# Grace_sFirstMicrocontroller.net
KiCad netlist of a schematic drawn in EAGLE
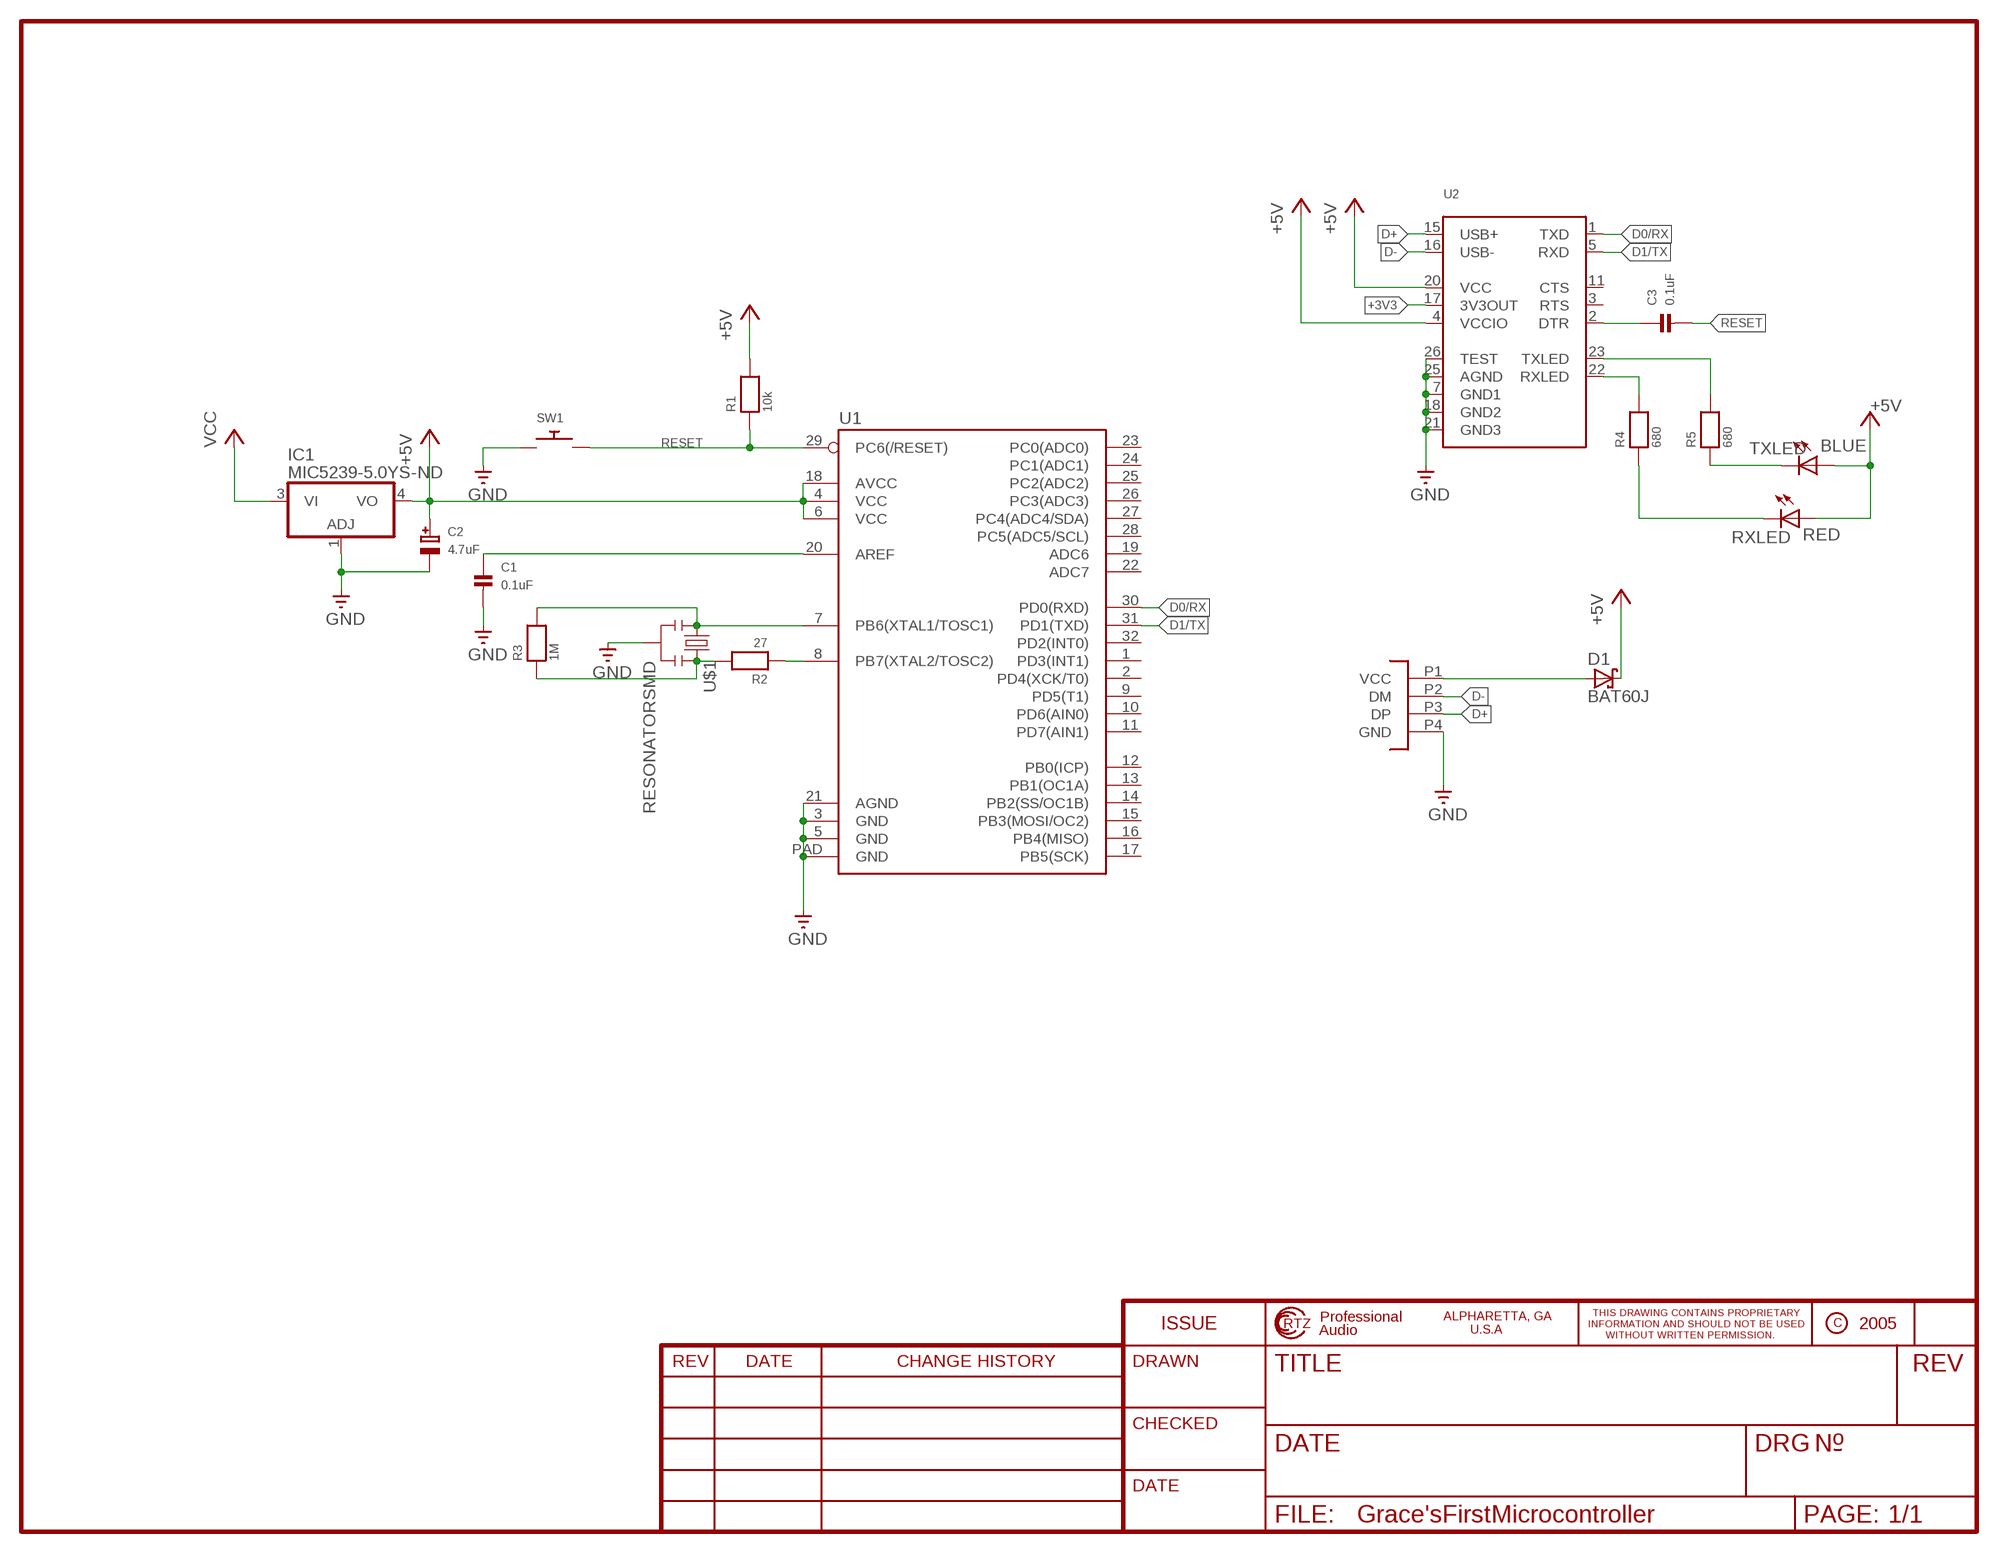
[diagram p0: schematic, sheet 1]

(export (version "E")
  (design (tool "Eeschema 10.0.6"))
  (components
    (comp (ref "C1")
      (value "0.1uF")
      (footprint "eagle-import:0603")
      (libsource (lib "eagle-import") (part "CAP_CERAMIC0603"))
    )
    (comp (ref "C2")
      (value "4.7uF")
      (footprint "eagle-import:EIA3216-18_A-R")
      (libsource (lib "eagle-import") (part "CAP_TANTALUMA/3216_REFLOW"))
    )
    (comp (ref "C3")
      (value "0.1uF")
      (footprint "eagle-import:0603")
      (libsource (lib "eagle-import") (part "CAP_CERAMIC0603"))
    )
    (comp (ref "D1")
      (value "BAT60J")
      (footprint "eagle-import:SOD323_ST")
      (libsource (lib "eagle-import") (part "BAT60J"))
    )
    (comp (ref "IC1")
      (value "MIC5239-5.0YS-ND")
      (footprint "eagle-import:SOT223")
      (libsource (lib "eagle-import") (part "317EMP"))
    )
    (comp (ref "J4A")
      (value "USB_TYPE_A_ONBOARD")
      (footprint "eagle-import:USB_TYPEA_ONBOARD")
      (libsource (lib "eagle-import") (part "USB_TYPE_A_ONBOARD"))
    )
    (comp (ref "R1")
      (value "10k")
      (footprint "eagle-import:0603")
      (libsource (lib "eagle-import") (part "RESISTOR0603"))
    )
    (comp (ref "R2")
      (value "27")
      (footprint "eagle-import:0603")
      (libsource (lib "eagle-import") (part "RESISTOR0603"))
    )
    (comp (ref "R3")
      (value "1M")
      (footprint "eagle-import:0603")
      (libsource (lib "eagle-import") (part "RESISTOR0603"))
    )
    (comp (ref "R4")
      (value "680")
      (footprint "eagle-import:0603")
      (libsource (lib "eagle-import") (part "RESISTOR0603"))
    )
    (comp (ref "R5")
      (value "680")
      (footprint "eagle-import:0603")
      (libsource (lib "eagle-import") (part "RESISTOR0603"))
    )
    (comp (ref "RXLED")
      (value "RED")
      (footprint "eagle-import:CHIPLED_0805")
      (libsource (lib "eagle-import") (part "LEDCHIPLED_0805"))
    )
    (comp (ref "SW1")
      (value "SWITCH_PUSHBUTTONEVQ-PE")
      (footprint "eagle-import:TACT_PANA-EVQ")
      (libsource (lib "eagle-import") (part "SWITCH_PUSHBUTTONEVQ-PE"))
    )
    (comp (ref "TXLED")
      (value "BLUE")
      (footprint "eagle-import:CHIPLED_0805")
      (libsource (lib "eagle-import") (part "LEDCHIPLED_0805"))
    )
    (comp (ref "U$1")
      (value "RESONATORSMD")
      (footprint "eagle-import:RESONATOR-SMD")
      (libsource (lib "eagle-import") (part "RESONATORSMD"))
    )
    (comp (ref "U1")
      (value "ATMEGA328P_MLFMLF32")
      (footprint "eagle-import:MLF32-PAD")
      (libsource (lib "eagle-import") (part "ATMEGA328P_MLFMLF32"))
    )
    (comp (ref "U2")
      (value "FT232RLSSOP28")
      (footprint "eagle-import:SSOP28DB")
      (libsource (lib "eagle-import") (part "FT232RLSSOP28"))
    )
  )
  (nets
    (net (code "1") (name "+3V3") (class "Default")
      (node (ref "U2") (pin "17") (pinfunction "3V3OUT_17") (pintype "power_in"))
    )
    (net (code "2") (name "+5V") (class "Default")
      (node (ref "C2") (pin "+") (pinfunction "+_+") (pintype "passive"))
      (node (ref "D1") (pin "C") (pinfunction "C_C") (pintype "passive"))
      (node (ref "IC1") (pin "4") (pinfunction "VO_4") (pintype "passive"))
      (node (ref "R1") (pin "2") (pinfunction "2_2") (pintype "passive"))
      (node (ref "RXLED") (pin "A") (pinfunction "A_A") (pintype "passive"))
      (node (ref "TXLED") (pin "A") (pinfunction "A_A") (pintype "passive"))
      (node (ref "U1") (pin "18") (pinfunction "AVCC_18") (pintype "bidirectional"))
      (node (ref "U1") (pin "4") (pinfunction "VCC_4") (pintype "bidirectional"))
      (node (ref "U1") (pin "6") (pinfunction "VCC_6") (pintype "bidirectional"))
      (node (ref "U2") (pin "20") (pinfunction "VCC_20") (pintype "power_in"))
      (node (ref "U2") (pin "4") (pinfunction "VCCIO_4") (pintype "power_in"))
    )
    (net (code "3") (name "D+") (class "Default")
      (node (ref "J4A") (pin "P3") (pinfunction "DP_P3") (pintype "bidirectional"))
      (node (ref "U2") (pin "15") (pinfunction "USB+_15") (pintype "bidirectional"))
    )
    (net (code "4") (name "D-") (class "Default")
      (node (ref "J4A") (pin "P2") (pinfunction "DM_P2") (pintype "bidirectional"))
      (node (ref "U2") (pin "16") (pinfunction "USB-_16") (pintype "bidirectional"))
    )
    (net (code "5") (name "D0{slash}RX") (class "Default")
      (node (ref "U1") (pin "30") (pinfunction "PD0(RXD)_30") (pintype "bidirectional"))
      (node (ref "U2") (pin "1") (pinfunction "TXD_1") (pintype "output"))
    )
    (net (code "6") (name "D1{slash}TX") (class "Default")
      (node (ref "U1") (pin "31") (pinfunction "PD1(TXD)_31") (pintype "bidirectional"))
      (node (ref "U2") (pin "5") (pinfunction "RXD_5") (pintype "input"))
    )
    (net (code "7") (name "GND") (class "Default")
      (node (ref "C1") (pin "2") (pinfunction "P$2_2") (pintype "passive"))
      (node (ref "C2") (pin "-") (pinfunction "-_-") (pintype "passive"))
      (node (ref "IC1") (pin "1") (pinfunction "ADJ_1") (pintype "input"))
      (node (ref "J4A") (pin "P4") (pinfunction "GND_P4") (pintype "bidirectional"))
      (node (ref "SW1") (pin "P$1") (pinfunction "P$1_P$1") (pintype "passive"))
      (node (ref "U$1") (pin "2") (pinfunction "2_2") (pintype "passive"))
      (node (ref "U1") (pin "21") (pinfunction "AGND_21") (pintype "bidirectional"))
      (node (ref "U1") (pin "3") (pinfunction "GND_3") (pintype "bidirectional"))
      (node (ref "U1") (pin "5") (pinfunction "GND_5") (pintype "bidirectional"))
      (node (ref "U1") (pin "PAD") (pinfunction "GND_PAD") (pintype "bidirectional"))
      (node (ref "U2") (pin "18") (pinfunction "GND2_18") (pintype "power_in"))
      (node (ref "U2") (pin "21") (pinfunction "GND3_21") (pintype "power_in"))
      (node (ref "U2") (pin "25") (pinfunction "AGND_25") (pintype "power_in"))
      (node (ref "U2") (pin "26") (pinfunction "TEST_26") (pintype "input"))
      (node (ref "U2") (pin "7") (pinfunction "GND1_7") (pintype "power_in"))
    )
    (net (code "8") (name "Net-(C1-P$1)") (class "Default")
      (node (ref "C1") (pin "1") (pinfunction "P$1_1") (pintype "passive"))
      (node (ref "U1") (pin "20") (pinfunction "AREF_20") (pintype "bidirectional"))
    )
    (net (code "9") (name "Net-(C3-P$1)") (class "Default")
      (node (ref "C3") (pin "1") (pinfunction "P$1_1") (pintype "passive"))
      (node (ref "U2") (pin "2") (pinfunction "DTR_2") (pintype "bidirectional"))
    )
    (net (code "10") (name "Net-(J4A-VCC)") (class "Default")
      (node (ref "D1") (pin "A") (pinfunction "A_A") (pintype "passive"))
      (node (ref "J4A") (pin "P1") (pinfunction "VCC_P1") (pintype "bidirectional"))
    )
    (net (code "11") (name "Net-(R2-Pad2)") (class "Default")
      (node (ref "R2") (pin "2") (pinfunction "2_2") (pintype "passive"))
      (node (ref "R3") (pin "1") (pinfunction "1_1") (pintype "passive"))
      (node (ref "U$1") (pin "3") (pinfunction "3_3") (pintype "passive"))
    )
    (net (code "12") (name "Net-(R4-Pad1)") (class "Default")
      (node (ref "R4") (pin "1") (pinfunction "1_1") (pintype "passive"))
      (node (ref "RXLED") (pin "C") (pinfunction "C_C") (pintype "passive"))
    )
    (net (code "13") (name "Net-(R5-Pad1)") (class "Default")
      (node (ref "R5") (pin "1") (pinfunction "1_1") (pintype "passive"))
      (node (ref "TXLED") (pin "C") (pinfunction "C_C") (pintype "passive"))
    )
    (net (code "14") (name "Net-(U1-PB6(XTAL1{slash}TOSC1))") (class "Default")
      (node (ref "R3") (pin "2") (pinfunction "2_2") (pintype "passive"))
      (node (ref "U$1") (pin "1") (pinfunction "1_1") (pintype "passive"))
      (node (ref "U1") (pin "7") (pinfunction "PB6(XTAL1/TOSC1)_7") (pintype "bidirectional"))
    )
    (net (code "15") (name "Net-(U1-PB7(XTAL2{slash}TOSC2))") (class "Default")
      (node (ref "R2") (pin "1") (pinfunction "1_1") (pintype "passive"))
      (node (ref "U1") (pin "8") (pinfunction "PB7(XTAL2/TOSC2)_8") (pintype "bidirectional"))
    )
    (net (code "16") (name "Net-(U2-RXLED)") (class "Default")
      (node (ref "R4") (pin "2") (pinfunction "2_2") (pintype "passive"))
      (node (ref "U2") (pin "22") (pinfunction "RXLED_22") (pintype "bidirectional"))
    )
    (net (code "17") (name "Net-(U2-TXLED)") (class "Default")
      (node (ref "R5") (pin "2") (pinfunction "2_2") (pintype "passive"))
      (node (ref "U2") (pin "23") (pinfunction "TXLED_23") (pintype "bidirectional"))
    )
    (net (code "18") (name "RESET") (class "Default")
      (node (ref "C3") (pin "2") (pinfunction "P$2_2") (pintype "passive"))
      (node (ref "R1") (pin "1") (pinfunction "1_1") (pintype "passive"))
      (node (ref "SW1") (pin "P$2") (pinfunction "P$2_P$2") (pintype "passive"))
      (node (ref "U1") (pin "29") (pinfunction "PC6(/RESET)_29") (pintype "bidirectional"))
    )
    (net (code "19") (name "VCC") (class "Default")
      (node (ref "IC1") (pin "3") (pinfunction "VI_3") (pintype "input"))
    )
    (net (code "20") (name "unconnected-(U1-ADC6-Pad19)") (class "Default")
      (node (ref "U1") (pin "19") (pinfunction "ADC6_19") (pintype "bidirectional"))
    )
    (net (code "21") (name "unconnected-(U1-ADC7-Pad22)") (class "Default")
      (node (ref "U1") (pin "22") (pinfunction "ADC7_22") (pintype "bidirectional"))
    )
    (net (code "22") (name "unconnected-(U1-PB0(ICP)-Pad12)") (class "Default")
      (node (ref "U1") (pin "12") (pinfunction "PB0(ICP)_12") (pintype "bidirectional"))
    )
    (net (code "23") (name "unconnected-(U1-PB1(OC1A)-Pad13)") (class "Default")
      (node (ref "U1") (pin "13") (pinfunction "PB1(OC1A)_13") (pintype "bidirectional"))
    )
    (net (code "24") (name "unconnected-(U1-PB2(SS{slash}OC1B)-Pad14)") (class "Default")
      (node (ref "U1") (pin "14") (pinfunction "PB2(SS/OC1B)_14") (pintype "bidirectional"))
    )
    (net (code "25") (name "unconnected-(U1-PB3(MOSI{slash}OC2)-Pad15)") (class "Default")
      (node (ref "U1") (pin "15") (pinfunction "PB3(MOSI/OC2)_15") (pintype "bidirectional"))
    )
    (net (code "26") (name "unconnected-(U1-PB4(MISO)-Pad16)") (class "Default")
      (node (ref "U1") (pin "16") (pinfunction "PB4(MISO)_16") (pintype "bidirectional"))
    )
    (net (code "27") (name "unconnected-(U1-PB5(SCK)-Pad17)") (class "Default")
      (node (ref "U1") (pin "17") (pinfunction "PB5(SCK)_17") (pintype "bidirectional"))
    )
    (net (code "28") (name "unconnected-(U1-PC0(ADC0)-Pad23)") (class "Default")
      (node (ref "U1") (pin "23") (pinfunction "PC0(ADC0)_23") (pintype "bidirectional"))
    )
    (net (code "29") (name "unconnected-(U1-PC1(ADC1)-Pad24)") (class "Default")
      (node (ref "U1") (pin "24") (pinfunction "PC1(ADC1)_24") (pintype "bidirectional"))
    )
    (net (code "30") (name "unconnected-(U1-PC2(ADC2)-Pad25)") (class "Default")
      (node (ref "U1") (pin "25") (pinfunction "PC2(ADC2)_25") (pintype "bidirectional"))
    )
    (net (code "31") (name "unconnected-(U1-PC3(ADC3)-Pad26)") (class "Default")
      (node (ref "U1") (pin "26") (pinfunction "PC3(ADC3)_26") (pintype "bidirectional"))
    )
    (net (code "32") (name "unconnected-(U1-PC4(ADC4{slash}SDA)-Pad27)") (class "Default")
      (node (ref "U1") (pin "27") (pinfunction "PC4(ADC4/SDA)_27") (pintype "bidirectional"))
    )
    (net (code "33") (name "unconnected-(U1-PC5(ADC5{slash}SCL)-Pad28)") (class "Default")
      (node (ref "U1") (pin "28") (pinfunction "PC5(ADC5/SCL)_28") (pintype "bidirectional"))
    )
    (net (code "34") (name "unconnected-(U1-PD2(INT0)-Pad32)") (class "Default")
      (node (ref "U1") (pin "32") (pinfunction "PD2(INT0)_32") (pintype "bidirectional"))
    )
    (net (code "35") (name "unconnected-(U1-PD3(INT1)-Pad1)") (class "Default")
      (node (ref "U1") (pin "1") (pinfunction "PD3(INT1)_1") (pintype "bidirectional"))
    )
    (net (code "36") (name "unconnected-(U1-PD4(XCK{slash}T0)-Pad2)") (class "Default")
      (node (ref "U1") (pin "2") (pinfunction "PD4(XCK/T0)_2") (pintype "bidirectional"))
    )
    (net (code "37") (name "unconnected-(U1-PD5(T1)-Pad9)") (class "Default")
      (node (ref "U1") (pin "9") (pinfunction "PD5(T1)_9") (pintype "bidirectional"))
    )
    (net (code "38") (name "unconnected-(U1-PD6(AIN0)-Pad10)") (class "Default")
      (node (ref "U1") (pin "10") (pinfunction "PD6(AIN0)_10") (pintype "bidirectional"))
    )
    (net (code "39") (name "unconnected-(U1-PD7(AIN1)-Pad11)") (class "Default")
      (node (ref "U1") (pin "11") (pinfunction "PD7(AIN1)_11") (pintype "bidirectional"))
    )
    (net (code "40") (name "unconnected-(U2-CTS-Pad11)") (class "Default")
      (node (ref "U2") (pin "11") (pinfunction "CTS_11") (pintype "bidirectional"))
    )
    (net (code "41") (name "unconnected-(U2-RTS-Pad3)") (class "Default")
      (node (ref "U2") (pin "3") (pinfunction "RTS_3") (pintype "bidirectional"))
    )
  )
)
